# SDRAM_MT48LC16M16A2TG_16Mx32.net
KiCad netlist of a schematic drawn in Altium Designer
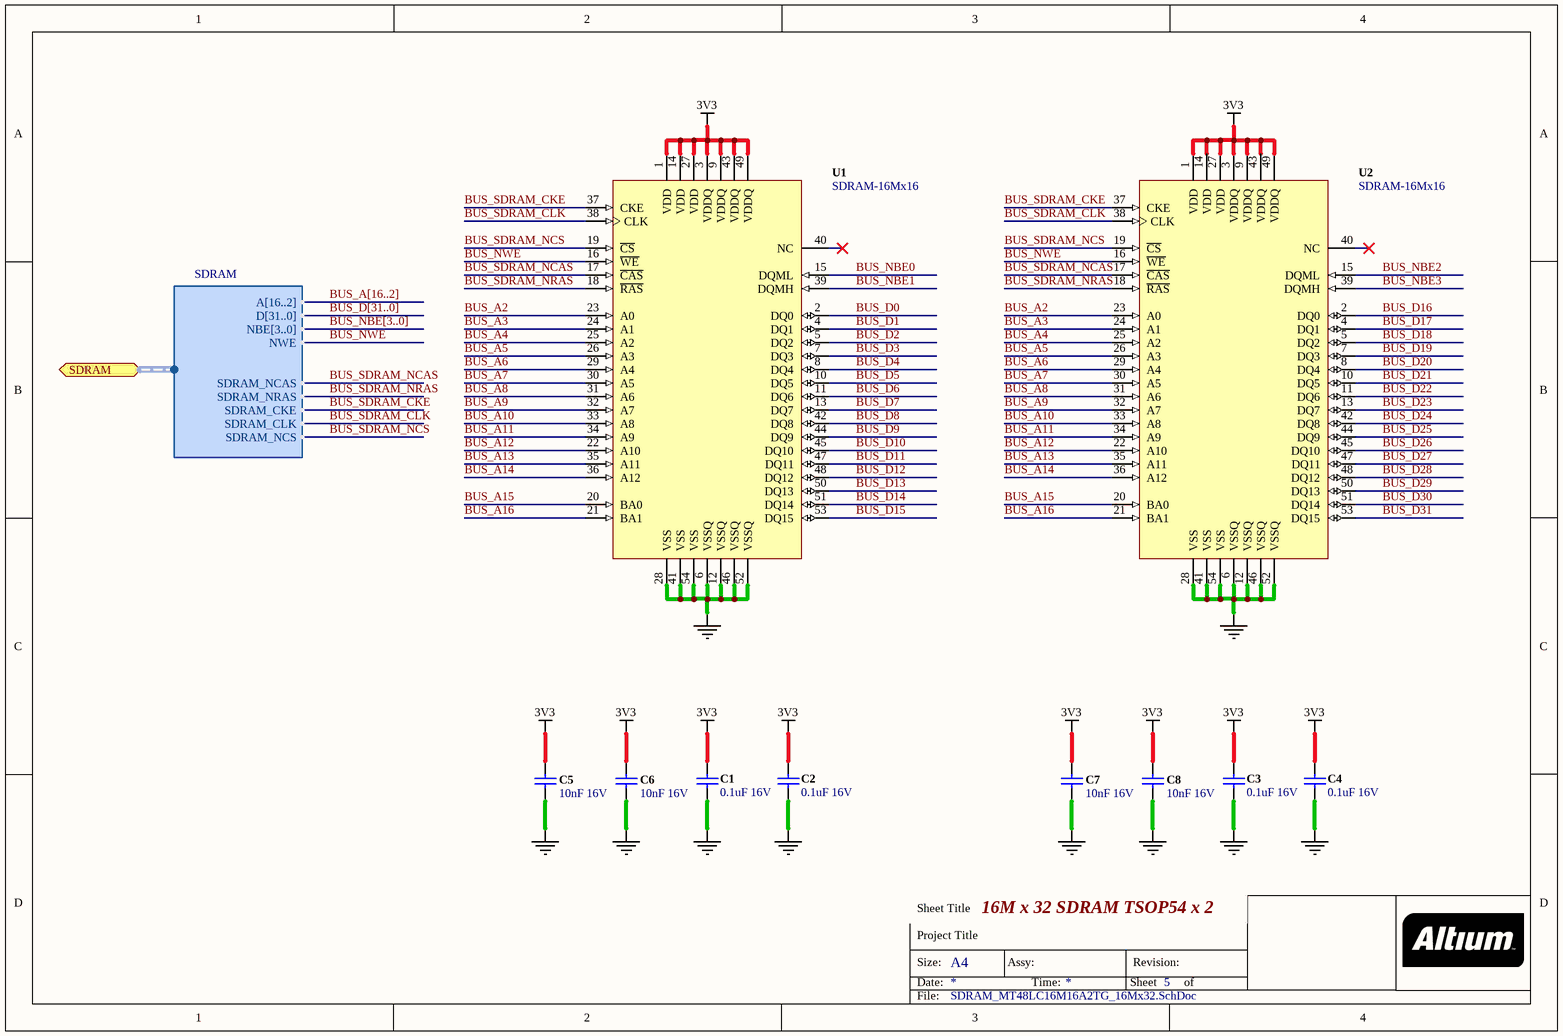
[diagram p0: SDRAM_MT48LC16M16A2TG_16Mx32.SchDoc]

(export (version "E")
  (design (tool "Eeschema 10.0.6"))
  (components
    (comp (ref "C1")
      (value "0.1uF 16V")
      (footprint "CAPC1005-STAR")
      (description "Capacitor, Ceramic, 0.1uF 10% 16V 0402 (1005) X7R")
      (fields (field (name "TOLERANCE") "10 %"))
      (libsource (lib "altium-import") (part "root_0_mirrored_CAP-NP_"))
    )
    (comp (ref "C2")
      (value "0.1uF 16V")
      (footprint "CAPC1005-STAR")
      (description "Capacitor, Ceramic, 0.1uF 10% 16V 0402 (1005) X7R")
      (fields (field (name "TOLERANCE") "10 %"))
      (libsource (lib "altium-import") (part "root_0_mirrored_CAP-NP_"))
    )
    (comp (ref "C3")
      (value "0.1uF 16V")
      (footprint "CAPC1005-STAR")
      (description "Capacitor, Ceramic, 0.1uF 10% 16V 0402 (1005) X7R")
      (fields (field (name "TOLERANCE") "10 %"))
      (libsource (lib "altium-import") (part "root_0_mirrored_CAP-NP_"))
    )
    (comp (ref "C4")
      (value "0.1uF 16V")
      (footprint "CAPC1005-STAR")
      (description "Capacitor, Ceramic, 0.1uF 10% 16V 0402 (1005) X7R")
      (fields (field (name "TOLERANCE") "10 %"))
      (libsource (lib "altium-import") (part "root_0_mirrored_CAP-NP_"))
    )
    (comp (ref "C5")
      (value "10nF 16V")
      (footprint "CAPC1005-STAR")
      (description "Capacitor, Ceramic, 10nF 10% 16V 0402 (1005) X7R")
      (fields (field (name "TOLERANCE") "10 %"))
      (libsource (lib "altium-import") (part "root_0_CAP-NP_"))
    )
    (comp (ref "C6")
      (value "10nF 16V")
      (footprint "CAPC1005-STAR")
      (description "Capacitor, Ceramic, 10nF 10% 16V 0402 (1005) X7R")
      (fields (field (name "TOLERANCE") "10 %"))
      (libsource (lib "altium-import") (part "root_0_CAP-NP_"))
    )
    (comp (ref "C7")
      (value "10nF 16V")
      (footprint "CAPC1005-STAR")
      (description "Capacitor, Ceramic, 10nF 10% 16V 0402 (1005) X7R")
      (fields (field (name "TOLERANCE") "10 %"))
      (libsource (lib "altium-import") (part "root_0_CAP-NP_"))
    )
    (comp (ref "C8")
      (value "10nF 16V")
      (footprint "CAPC1005-STAR")
      (description "Capacitor, Ceramic, 10nF 10% 16V 0402 (1005) X7R")
      (fields (field (name "TOLERANCE") "10 %"))
      (libsource (lib "altium-import") (part "root_0_CAP-NP_"))
    )
    (comp (ref "U1")
      (value "SDRAM-16Mx16")
      (footprint "TSOP80P1176-54")
      (description "MT48LC16M16A2TG, 256 Mbit High-Speed CMOS SDRAM, 16Mb x 16Bit x 4 Banks, TSOP54")
      (libsource (lib "altium-import") (part "root_0_MT48LC16M16A2TG_"))
    )
    (comp (ref "U2")
      (value "SDRAM-16Mx16")
      (footprint "TSOP80P1176-54")
      (description "MT48LC16M16A2TG, 256 Mbit High-Speed CMOS SDRAM, 16Mb x 16Bit x 4 Banks, TSOP54")
      (libsource (lib "altium-import") (part "root_0_MT48LC16M16A2TG_"))
    )
  )
  (nets
    (net (code "2") (name "/BUS_A2") (class "Default")
      (node (ref "U1") (pin "23") (pinfunction "A0_23") (pintype "input"))
      (node (ref "U2") (pin "23") (pinfunction "A0_23") (pintype "input"))
    )
    (net (code "3") (name "/BUS_A3") (class "Default")
      (node (ref "U1") (pin "24") (pinfunction "A1_24") (pintype "input"))
      (node (ref "U2") (pin "24") (pinfunction "A1_24") (pintype "input"))
    )
    (net (code "4") (name "/BUS_A4") (class "Default")
      (node (ref "U1") (pin "25") (pinfunction "A2_25") (pintype "input"))
      (node (ref "U2") (pin "25") (pinfunction "A2_25") (pintype "input"))
    )
    (net (code "5") (name "/BUS_A5") (class "Default")
      (node (ref "U1") (pin "26") (pinfunction "A3_26") (pintype "input"))
      (node (ref "U2") (pin "26") (pinfunction "A3_26") (pintype "input"))
    )
    (net (code "6") (name "/BUS_A6") (class "Default")
      (node (ref "U1") (pin "29") (pinfunction "A4_29") (pintype "input"))
      (node (ref "U2") (pin "29") (pinfunction "A4_29") (pintype "input"))
    )
    (net (code "7") (name "/BUS_A7") (class "Default")
      (node (ref "U1") (pin "30") (pinfunction "A5_30") (pintype "input"))
      (node (ref "U2") (pin "30") (pinfunction "A5_30") (pintype "input"))
    )
    (net (code "8") (name "/BUS_A8") (class "Default")
      (node (ref "U1") (pin "31") (pinfunction "A6_31") (pintype "input"))
      (node (ref "U2") (pin "31") (pinfunction "A6_31") (pintype "input"))
    )
    (net (code "9") (name "/BUS_A9") (class "Default")
      (node (ref "U1") (pin "32") (pinfunction "A7_32") (pintype "input"))
      (node (ref "U2") (pin "32") (pinfunction "A7_32") (pintype "input"))
    )
    (net (code "10") (name "/BUS_A10") (class "Default")
      (node (ref "U1") (pin "33") (pinfunction "A8_33") (pintype "input"))
      (node (ref "U2") (pin "33") (pinfunction "A8_33") (pintype "input"))
    )
    (net (code "11") (name "/BUS_A11") (class "Default")
      (node (ref "U1") (pin "34") (pinfunction "A9_34") (pintype "input"))
      (node (ref "U2") (pin "34") (pinfunction "A9_34") (pintype "input"))
    )
    (net (code "12") (name "/BUS_A12") (class "Default")
      (node (ref "U1") (pin "22") (pinfunction "A10_22") (pintype "input"))
      (node (ref "U2") (pin "22") (pinfunction "A10_22") (pintype "input"))
    )
    (net (code "13") (name "/BUS_A13") (class "Default")
      (node (ref "U1") (pin "35") (pinfunction "A11_35") (pintype "input"))
      (node (ref "U2") (pin "35") (pinfunction "A11_35") (pintype "input"))
    )
    (net (code "14") (name "/BUS_A14") (class "Default")
      (node (ref "U1") (pin "36") (pinfunction "A12_36") (pintype "input"))
      (node (ref "U2") (pin "36") (pinfunction "A12_36") (pintype "input"))
    )
    (net (code "15") (name "/BUS_A15") (class "Default")
      (node (ref "U1") (pin "20") (pinfunction "BA0_20") (pintype "input"))
      (node (ref "U2") (pin "20") (pinfunction "BA0_20") (pintype "input"))
    )
    (net (code "16") (name "/BUS_A16") (class "Default")
      (node (ref "U1") (pin "21") (pinfunction "BA1_21") (pintype "input"))
      (node (ref "U2") (pin "21") (pinfunction "BA1_21") (pintype "input"))
    )
    (net (code "18") (name "/BUS_D0") (class "Default")
      (node (ref "U1") (pin "2") (pinfunction "DQ0_2") (pintype "bidirectional"))
    )
    (net (code "19") (name "/BUS_D1") (class "Default")
      (node (ref "U1") (pin "4") (pinfunction "DQ1_4") (pintype "bidirectional"))
    )
    (net (code "20") (name "/BUS_D2") (class "Default")
      (node (ref "U1") (pin "5") (pinfunction "DQ2_5") (pintype "bidirectional"))
    )
    (net (code "21") (name "/BUS_D3") (class "Default")
      (node (ref "U1") (pin "7") (pinfunction "DQ3_7") (pintype "bidirectional"))
    )
    (net (code "22") (name "/BUS_D4") (class "Default")
      (node (ref "U1") (pin "8") (pinfunction "DQ4_8") (pintype "bidirectional"))
    )
    (net (code "23") (name "/BUS_D5") (class "Default")
      (node (ref "U1") (pin "10") (pinfunction "DQ5_10") (pintype "bidirectional"))
    )
    (net (code "24") (name "/BUS_D6") (class "Default")
      (node (ref "U1") (pin "11") (pinfunction "DQ6_11") (pintype "bidirectional"))
    )
    (net (code "25") (name "/BUS_D7") (class "Default")
      (node (ref "U1") (pin "13") (pinfunction "DQ7_13") (pintype "bidirectional"))
    )
    (net (code "26") (name "/BUS_D8") (class "Default")
      (node (ref "U1") (pin "42") (pinfunction "DQ8_42") (pintype "bidirectional"))
    )
    (net (code "27") (name "/BUS_D9") (class "Default")
      (node (ref "U1") (pin "44") (pinfunction "DQ9_44") (pintype "bidirectional"))
    )
    (net (code "28") (name "/BUS_D10") (class "Default")
      (node (ref "U1") (pin "45") (pinfunction "DQ10_45") (pintype "bidirectional"))
    )
    (net (code "29") (name "/BUS_D11") (class "Default")
      (node (ref "U1") (pin "47") (pinfunction "DQ11_47") (pintype "bidirectional"))
    )
    (net (code "30") (name "/BUS_D12") (class "Default")
      (node (ref "U1") (pin "48") (pinfunction "DQ12_48") (pintype "bidirectional"))
    )
    (net (code "31") (name "/BUS_D13") (class "Default")
      (node (ref "U1") (pin "50") (pinfunction "DQ13_50") (pintype "bidirectional"))
    )
    (net (code "32") (name "/BUS_D14") (class "Default")
      (node (ref "U1") (pin "51") (pinfunction "DQ14_51") (pintype "bidirectional"))
    )
    (net (code "33") (name "/BUS_D15") (class "Default")
      (node (ref "U1") (pin "53") (pinfunction "DQ15_53") (pintype "bidirectional"))
    )
    (net (code "34") (name "/BUS_D16") (class "Default")
      (node (ref "U2") (pin "2") (pinfunction "DQ0_2") (pintype "bidirectional"))
    )
    (net (code "35") (name "/BUS_D17") (class "Default")
      (node (ref "U2") (pin "4") (pinfunction "DQ1_4") (pintype "bidirectional"))
    )
    (net (code "36") (name "/BUS_D18") (class "Default")
      (node (ref "U2") (pin "5") (pinfunction "DQ2_5") (pintype "bidirectional"))
    )
    (net (code "37") (name "/BUS_D19") (class "Default")
      (node (ref "U2") (pin "7") (pinfunction "DQ3_7") (pintype "bidirectional"))
    )
    (net (code "38") (name "/BUS_D20") (class "Default")
      (node (ref "U2") (pin "8") (pinfunction "DQ4_8") (pintype "bidirectional"))
    )
    (net (code "39") (name "/BUS_D21") (class "Default")
      (node (ref "U2") (pin "10") (pinfunction "DQ5_10") (pintype "bidirectional"))
    )
    (net (code "40") (name "/BUS_D22") (class "Default")
      (node (ref "U2") (pin "11") (pinfunction "DQ6_11") (pintype "bidirectional"))
    )
    (net (code "41") (name "/BUS_D23") (class "Default")
      (node (ref "U2") (pin "13") (pinfunction "DQ7_13") (pintype "bidirectional"))
    )
    (net (code "42") (name "/BUS_D24") (class "Default")
      (node (ref "U2") (pin "42") (pinfunction "DQ8_42") (pintype "bidirectional"))
    )
    (net (code "43") (name "/BUS_D25") (class "Default")
      (node (ref "U2") (pin "44") (pinfunction "DQ9_44") (pintype "bidirectional"))
    )
    (net (code "44") (name "/BUS_D26") (class "Default")
      (node (ref "U2") (pin "45") (pinfunction "DQ10_45") (pintype "bidirectional"))
    )
    (net (code "45") (name "/BUS_D27") (class "Default")
      (node (ref "U2") (pin "47") (pinfunction "DQ11_47") (pintype "bidirectional"))
    )
    (net (code "46") (name "/BUS_D28") (class "Default")
      (node (ref "U2") (pin "48") (pinfunction "DQ12_48") (pintype "bidirectional"))
    )
    (net (code "47") (name "/BUS_D29") (class "Default")
      (node (ref "U2") (pin "50") (pinfunction "DQ13_50") (pintype "bidirectional"))
    )
    (net (code "48") (name "/BUS_D30") (class "Default")
      (node (ref "U2") (pin "51") (pinfunction "DQ14_51") (pintype "bidirectional"))
    )
    (net (code "49") (name "/BUS_D31") (class "Default")
      (node (ref "U2") (pin "53") (pinfunction "DQ15_53") (pintype "bidirectional"))
    )
    (net (code "51") (name "/BUS_NBE0") (class "Default")
      (node (ref "U1") (pin "15") (pinfunction "DQML_15") (pintype "input"))
    )
    (net (code "52") (name "/BUS_NBE1") (class "Default")
      (node (ref "U1") (pin "39") (pinfunction "DQMH_39") (pintype "input"))
    )
    (net (code "53") (name "/BUS_NBE2") (class "Default")
      (node (ref "U2") (pin "15") (pinfunction "DQML_15") (pintype "input"))
    )
    (net (code "54") (name "/BUS_NBE3") (class "Default")
      (node (ref "U2") (pin "39") (pinfunction "DQMH_39") (pintype "input"))
    )
    (net (code "56") (name "/BUS_NWE") (class "Default")
      (node (ref "U1") (pin "16") (pinfunction "~{WE}_16") (pintype "input"))
      (node (ref "U2") (pin "16") (pinfunction "~{WE}_16") (pintype "input"))
    )
    (net (code "57") (name "/BUS_SDRAM_CKE") (class "Default")
      (node (ref "U1") (pin "37") (pinfunction "CKE_37") (pintype "input"))
      (node (ref "U2") (pin "37") (pinfunction "CKE_37") (pintype "input"))
    )
    (net (code "58") (name "/BUS_SDRAM_CLK") (class "Default")
      (node (ref "U1") (pin "38") (pinfunction "CLK_38") (pintype "input"))
      (node (ref "U2") (pin "38") (pinfunction "CLK_38") (pintype "input"))
    )
    (net (code "59") (name "/BUS_SDRAM_NCAS") (class "Default")
      (node (ref "U1") (pin "17") (pinfunction "~{CAS}_17") (pintype "input"))
      (node (ref "U2") (pin "17") (pinfunction "~{CAS}_17") (pintype "input"))
    )
    (net (code "60") (name "/BUS_SDRAM_NCS") (class "Default")
      (node (ref "U1") (pin "19") (pinfunction "~{CS}_19") (pintype "input"))
      (node (ref "U2") (pin "19") (pinfunction "~{CS}_19") (pintype "input"))
    )
    (net (code "61") (name "/BUS_SDRAM_NRAS") (class "Default")
      (node (ref "U1") (pin "18") (pinfunction "~{RAS}_18") (pintype "input"))
      (node (ref "U2") (pin "18") (pinfunction "~{RAS}_18") (pintype "input"))
    )
    (net (code "63") (name "3V3") (class "Default")
      (node (ref "C1") (pin "1") (pinfunction "1_1") (pintype "passive"))
      (node (ref "C2") (pin "1") (pinfunction "1_1") (pintype "passive"))
      (node (ref "C3") (pin "1") (pinfunction "1_1") (pintype "passive"))
      (node (ref "C4") (pin "1") (pinfunction "1_1") (pintype "passive"))
      (node (ref "C5") (pin "1") (pinfunction "1_1") (pintype "passive"))
      (node (ref "C6") (pin "1") (pinfunction "1_1") (pintype "passive"))
      (node (ref "C7") (pin "1") (pinfunction "1_1") (pintype "passive"))
      (node (ref "C8") (pin "1") (pinfunction "1_1") (pintype "passive"))
      (node (ref "U1") (pin "1") (pinfunction "VDD_1") (pintype "power_in"))
      (node (ref "U1") (pin "14") (pinfunction "VDD_14") (pintype "power_in"))
      (node (ref "U1") (pin "27") (pinfunction "VDD_27") (pintype "power_in"))
      (node (ref "U1") (pin "3") (pinfunction "VDDQ_3") (pintype "power_in"))
      (node (ref "U1") (pin "43") (pinfunction "VDDQ_43") (pintype "power_in"))
      (node (ref "U1") (pin "49") (pinfunction "VDDQ_49") (pintype "power_in"))
      (node (ref "U1") (pin "9") (pinfunction "VDDQ_9") (pintype "power_in"))
      (node (ref "U2") (pin "1") (pinfunction "VDD_1") (pintype "power_in"))
      (node (ref "U2") (pin "14") (pinfunction "VDD_14") (pintype "power_in"))
      (node (ref "U2") (pin "27") (pinfunction "VDD_27") (pintype "power_in"))
      (node (ref "U2") (pin "3") (pinfunction "VDDQ_3") (pintype "power_in"))
      (node (ref "U2") (pin "43") (pinfunction "VDDQ_43") (pintype "power_in"))
      (node (ref "U2") (pin "49") (pinfunction "VDDQ_49") (pintype "power_in"))
      (node (ref "U2") (pin "9") (pinfunction "VDDQ_9") (pintype "power_in"))
    )
    (net (code "64") (name "GND") (class "Default")
      (node (ref "C1") (pin "2") (pinfunction "2_2") (pintype "passive"))
      (node (ref "C2") (pin "2") (pinfunction "2_2") (pintype "passive"))
      (node (ref "C3") (pin "2") (pinfunction "2_2") (pintype "passive"))
      (node (ref "C4") (pin "2") (pinfunction "2_2") (pintype "passive"))
      (node (ref "C5") (pin "2") (pinfunction "2_2") (pintype "passive"))
      (node (ref "C6") (pin "2") (pinfunction "2_2") (pintype "passive"))
      (node (ref "C7") (pin "2") (pinfunction "2_2") (pintype "passive"))
      (node (ref "C8") (pin "2") (pinfunction "2_2") (pintype "passive"))
      (node (ref "U1") (pin "12") (pinfunction "VSSQ_12") (pintype "power_in"))
      (node (ref "U1") (pin "28") (pinfunction "VSS_28") (pintype "power_in"))
      (node (ref "U1") (pin "41") (pinfunction "VSS_41") (pintype "power_in"))
      (node (ref "U1") (pin "46") (pinfunction "VSSQ_46") (pintype "power_in"))
      (node (ref "U1") (pin "52") (pinfunction "VSSQ_52") (pintype "power_in"))
      (node (ref "U1") (pin "54") (pinfunction "VSS_54") (pintype "power_in"))
      (node (ref "U1") (pin "6") (pinfunction "VSSQ_6") (pintype "power_in"))
      (node (ref "U2") (pin "12") (pinfunction "VSSQ_12") (pintype "power_in"))
      (node (ref "U2") (pin "28") (pinfunction "VSS_28") (pintype "power_in"))
      (node (ref "U2") (pin "41") (pinfunction "VSS_41") (pintype "power_in"))
      (node (ref "U2") (pin "46") (pinfunction "VSSQ_46") (pintype "power_in"))
      (node (ref "U2") (pin "52") (pinfunction "VSSQ_52") (pintype "power_in"))
      (node (ref "U2") (pin "54") (pinfunction "VSS_54") (pintype "power_in"))
      (node (ref "U2") (pin "6") (pinfunction "VSSQ_6") (pintype "power_in"))
    )
    (net (code "65") (name "unconnected-(U1-NC-Pad40)") (class "Default")
      (node (ref "U1") (pin "40") (pinfunction "NC_40") (pintype "passive+no_connect"))
    )
    (net (code "66") (name "unconnected-(U2-NC-Pad40)") (class "Default")
      (node (ref "U2") (pin "40") (pinfunction "NC_40") (pintype "passive+no_connect"))
    )
  )
)
